# power_supply.net
KiCad netlist of a schematic drawn in Altium Designer
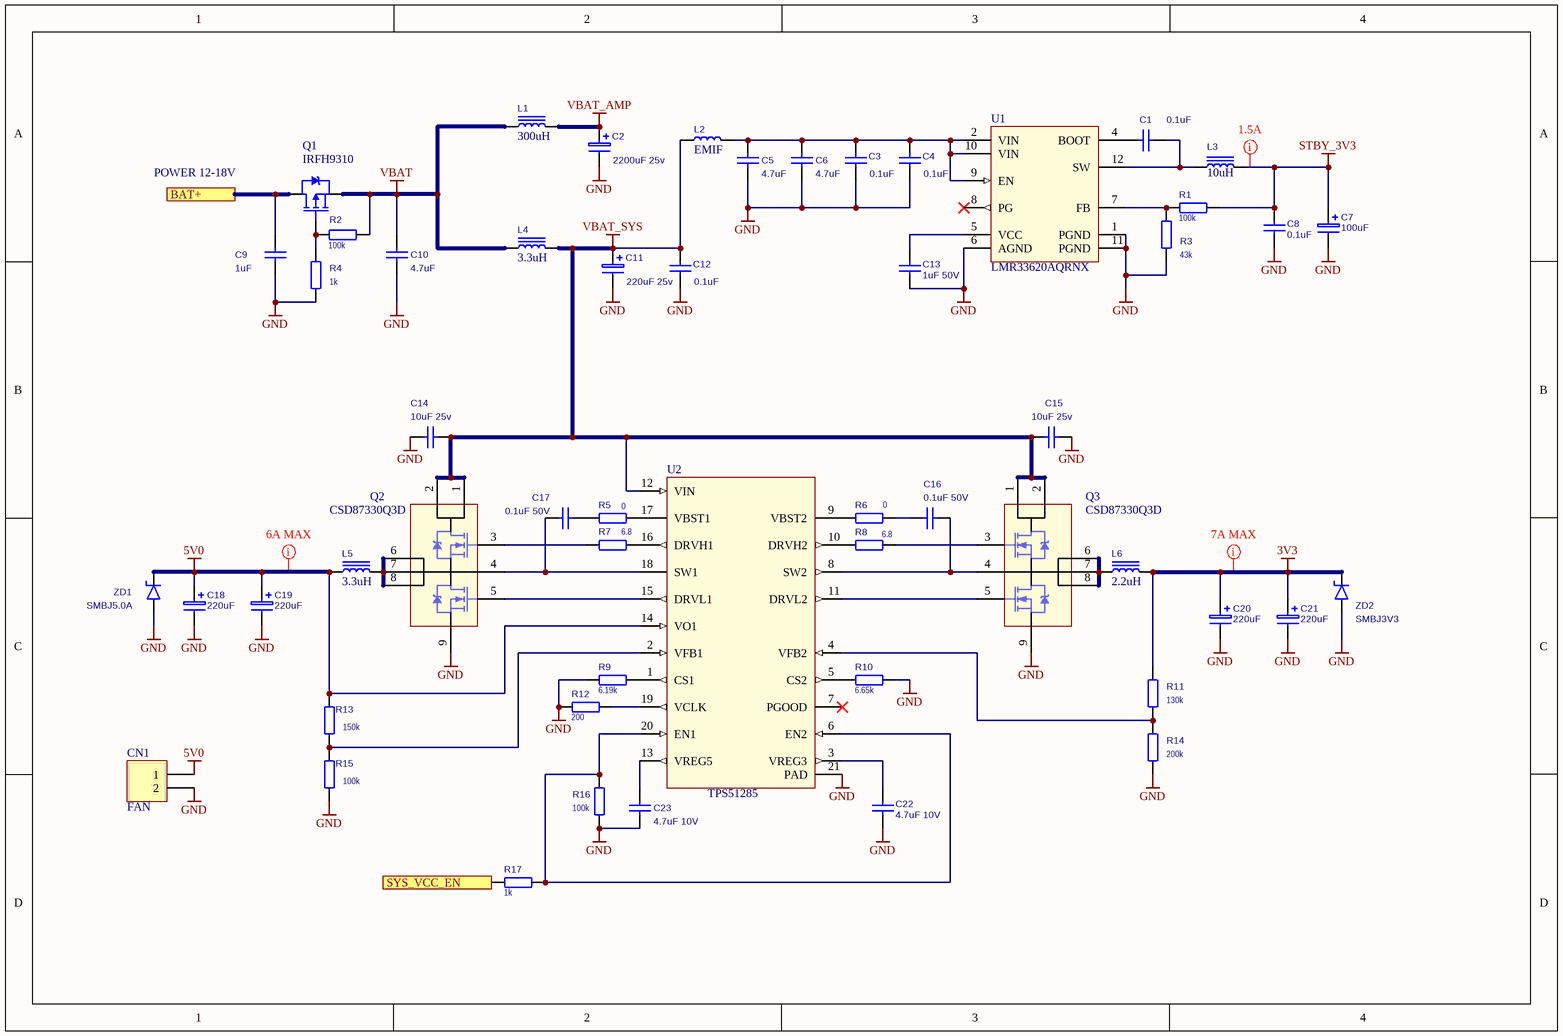
[diagram p0: power_supply.SchDoc]

(export (version "E")
  (design (tool "Eeschema 10.0.6"))
  (components
    (comp (ref "C1")
      (value "0.1uF")
      (footprint "Capacitors:C0603")
      (description "CAP_NPOL")
      (fields (field (name "Comment") "C1608X7R1H104K080AA"))
      (libsource (lib "capacitors") (part "CAP_NPOL"))
    )
    (comp (ref "C2")
      (value "2200uF 25v")
      (footprint "R12H05")
      (description "CAP_POL")
      (fields (field (name "Comment") "EEU-FC1V222"))
      (libsource (lib "capacitors") (part "CAP_POL"))
    )
    (comp (ref "C3")
      (value "0.1uF")
      (footprint "Capacitors:C0603")
      (description "CAP_NPOL")
      (fields (field (name "Comment") "C1608X7R1H104K080AA"))
      (libsource (lib "capacitors") (part "CAP_NPOL"))
    )
    (comp (ref "C4")
      (value "0.1uF")
      (footprint "Capacitors:C0603")
      (description "CAP_NPOL")
      (fields (field (name "Comment") "C1608X7R1H104K080AA"))
      (libsource (lib "capacitors") (part "CAP_NPOL"))
    )
    (comp (ref "C5")
      (value "4.7uF")
      (footprint "Capacitors:C0603")
      (description "CAP_NPOL")
      (fields (field (name "Comment") "GRM188R61E475KE11D"))
      (libsource (lib "capacitors") (part "CAP_NPOL"))
    )
    (comp (ref "C6")
      (value "4.7uF")
      (footprint "Capacitors:C0603")
      (description "CAP_NPOL")
      (fields (field (name "Comment") "GRM188R61E475KE11D"))
      (libsource (lib "capacitors") (part "CAP_NPOL"))
    )
    (comp (ref "C7")
      (value "100uF")
      (footprint "Capacitors:TANTAL-B-1411")
      (description "CAP_POL")
      (fields (field (name "Comment") "6TPE100MPB"))
      (libsource (lib "capacitors") (part "CAP_POL"))
    )
    (comp (ref "C8")
      (value "0.1uF")
      (footprint "Capacitors:C0603")
      (description "CAP_NPOL")
      (fields (field (name "Comment") "C1608X7R1H104K080AA"))
      (libsource (lib "capacitors") (part "CAP_NPOL"))
    )
    (comp (ref "C9")
      (value "1uF")
      (footprint "Capacitors:C0603")
      (description "CAP_NPOL")
      (fields (field (name "Comment") "CC0603KRX7R9BB105"))
      (libsource (lib "capacitors") (part "CAP_NPOL"))
    )
    (comp (ref "C10")
      (value "4.7uF")
      (footprint "Capacitors:C0603")
      (description "CAP_NPOL")
      (fields (field (name "Comment") "GRM188R61E475KE11D"))
      (libsource (lib "capacitors") (part "CAP_NPOL"))
    )
    (comp (ref "C11")
      (value "220uF 25v")
      (footprint "Capacitors:R08H04")
      (description "CAP_POL")
      (fields (field (name "Comment") "ECAP 220/25V 0812 105'C"))
      (libsource (lib "capacitors") (part "CAP_POL"))
    )
    (comp (ref "C12")
      (value "0.1uF")
      (footprint "Capacitors:C0603")
      (description "CAP_NPOL")
      (fields (field (name "Comment") "C1608X7R1H104K080AA"))
      (libsource (lib "capacitors") (part "CAP_NPOL"))
    )
    (comp (ref "C13")
      (value "1uF 50V")
      (footprint "Capacitors:C0603")
      (description "CAP_NPOL")
      (fields (field (name "Comment") "CC0603KRX7R9BB105"))
      (libsource (lib "capacitors") (part "CAP_NPOL"))
    )
    (comp (ref "C14")
      (value "10uF 25v")
      (footprint "Capacitors:C0805")
      (description "CAP_NPOL")
      (fields (field (name "Comment") "GRM21BR61E106KA73L"))
      (libsource (lib "capacitors") (part "CAP_NPOL"))
    )
    (comp (ref "C15")
      (value "10uF 25v")
      (footprint "Capacitors:C0805")
      (description "CAP_NPOL")
      (fields (field (name "Comment") "GRM21BR61E106KA73L"))
      (libsource (lib "capacitors") (part "CAP_NPOL"))
    )
    (comp (ref "C16")
      (value "0.1uF 50V")
      (footprint "Capacitors:C0603")
      (description "CAP_NPOL")
      (fields (field (name "Comment") "C1608X7R1H104K080AA"))
      (libsource (lib "capacitors") (part "CAP_NPOL"))
    )
    (comp (ref "C17")
      (value "0.1uF 50V")
      (footprint "Capacitors:C0603")
      (description "CAP_NPOL")
      (fields (field (name "Comment") "C1608X7R1H104K080AA"))
      (libsource (lib "capacitors") (part "CAP_NPOL"))
    )
    (comp (ref "C18")
      (value "220uF")
      (footprint "Capacitors:TANTAL-D-2916")
      (description "CAP_POL")
      (fields (field (name "Comment") "6TPE220MI"))
      (libsource (lib "capacitors") (part "CAP_POL"))
    )
    (comp (ref "C19")
      (value "220uF")
      (footprint "Capacitors:TANTAL-D-2916")
      (description "CAP_POL")
      (fields (field (name "Comment") "6TPE220MI"))
      (libsource (lib "capacitors") (part "CAP_POL"))
    )
    (comp (ref "C20")
      (value "220uF")
      (footprint "Capacitors:TANTAL-D-2916")
      (description "CAP_POL")
      (fields (field (name "Comment") "6TPE220MI"))
      (libsource (lib "capacitors") (part "CAP_POL"))
    )
    (comp (ref "C21")
      (value "220uF")
      (footprint "Capacitors:TANTAL-D-2916")
      (description "CAP_POL")
      (fields (field (name "Comment") "6TPE220MI"))
      (libsource (lib "capacitors") (part "CAP_POL"))
    )
    (comp (ref "C22")
      (value "4.7uF 10V")
      (footprint "Capacitors:C0603")
      (description "CAP_NPOL")
      (fields (field (name "Comment") "CL10A475KP8NNNC"))
      (libsource (lib "capacitors") (part "CAP_NPOL"))
    )
    (comp (ref "C23")
      (value "4.7uF 10V")
      (footprint "Capacitors:C0603")
      (description "CAP_NPOL")
      (fields (field (name "Comment") "CL10A475KP8NNNC"))
      (libsource (lib "capacitors") (part "CAP_NPOL"))
    )
    (comp (ref "CN1")
      (value "FAN")
      (footprint "HDR:MW-2M")
      (description "Header, 2-Pin")
      (fields (field (name "PUBLISHER") "Altium Limited"))
      (libsource (lib "HDR") (part "HDR 2"))
    )
    (comp (ref "L1")
      (value "300uH")
      (footprint "IND_COIL_TH_33x18")
      (description "IND_W_IRON")
      (fields (field (name "Comment") "ATCA-06-301M"))
      (libsource (lib "inductors") (part "IND_W_IRON"))
    )
    (comp (ref "L2")
      (value "EMIF")
      (footprint "IND0805")
      (description "IND_WO_IRON")
      (fields (field (name "Comment") "BLM21PG221SN1D"))
      (libsource (lib "inductors") (part "IND_WO_IRON"))
    )
    (comp (ref "L3")
      (value "10uH")
      (footprint "CDRH6D28")
      (fields (field (name "Comment") "CDRH6D38NP-100NC"))
      (libsource (lib "inductors") (part "IND_W_IRON"))
    )
    (comp (ref "L4")
      (value "3.3uH")
      (footprint "IHLP-2525CZ")
      (description "IND_W_IRON")
      (fields (field (name "Comment") "IHLP2525CZER3R3M01"))
      (libsource (lib "inductors") (part "IND_W_IRON"))
    )
    (comp (ref "L5")
      (value "3.3uH")
      (footprint "IHLP-2525CZ")
      (description "IND_W_IRON")
      (fields (field (name "Comment") "IHLP2525CZER3R3M01"))
      (libsource (lib "inductors") (part "IND_W_IRON"))
    )
    (comp (ref "L6")
      (value "2.2uH")
      (footprint "IHLP-2525CZ")
      (description "IND_W_IRON")
      (fields (field (name "Comment") "IHLP2525CZER2R2M01"))
      (libsource (lib "inductors") (part "IND_W_IRON"))
    )
    (comp (ref "Q1")
      (value "IRFH9310")
      (footprint "PQFN_5X6")
      (description "HEXFET Power MOSFET")
      (libsource (lib "MOSFET") (part "P-Channel"))
    )
    (comp (ref "Q2")
      (value "CSD87330Q3D")
      (footprint "SON:SON-8-3.3X3.3")
      (description "Synchronous Buck NexFET™ Power Block")
      (libsource (lib "CSD87330") (part "CSD87330Q3D"))
    )
    (comp (ref "Q3")
      (value "CSD87330Q3D")
      (footprint "SON:SON-8-3.3X3.3")
      (description "Synchronous Buck NexFET™ Power Block")
      (libsource (lib "CSD87330") (part "CSD87330Q3D"))
    )
    (comp (ref "R1")
      (value "100k")
      (footprint "R0603")
      (description "RES")
      (libsource (lib "resistors") (part "RESISTOR"))
    )
    (comp (ref "R2")
      (value "100k")
      (footprint "R0603")
      (description "RES")
      (libsource (lib "resistors") (part "RESISTOR"))
    )
    (comp (ref "R3")
      (value "43k")
      (footprint "R0603")
      (description "RES")
      (libsource (lib "resistors") (part "RESISTOR"))
    )
    (comp (ref "R4")
      (value "1k")
      (footprint "R0603")
      (description "RES")
      (libsource (lib "resistors") (part "RESISTOR"))
    )
    (comp (ref "R5")
      (value "0")
      (footprint "R0603")
      (description "RES")
      (libsource (lib "resistors") (part "RESISTOR"))
    )
    (comp (ref "R6")
      (value "0")
      (footprint "R0603")
      (description "RES")
      (libsource (lib "resistors") (part "RESISTOR"))
    )
    (comp (ref "R7")
      (value "6.8")
      (footprint "R0603")
      (description "RES")
      (fields (field (name "Comment") "RES 0603 6R8 5%"))
      (libsource (lib "resistors") (part "RESISTOR"))
    )
    (comp (ref "R8")
      (value "6.8")
      (footprint "R0603")
      (description "RES")
      (fields (field (name "Comment") "RES 0603 6R8 5%"))
      (libsource (lib "resistors") (part "RESISTOR"))
    )
    (comp (ref "R9")
      (value "6.19k")
      (footprint "R0603")
      (description "RES")
      (libsource (lib "resistors") (part "RESISTOR"))
    )
    (comp (ref "R10")
      (value "6.65k")
      (footprint "R0603")
      (description "RES")
      (libsource (lib "resistors") (part "RESISTOR"))
    )
    (comp (ref "R11")
      (value "130k")
      (footprint "R0603")
      (description "RES")
      (libsource (lib "resistors") (part "RESISTOR"))
    )
    (comp (ref "R12")
      (value "200")
      (footprint "R0603")
      (description "RES")
      (libsource (lib "resistors") (part "RESISTOR"))
    )
    (comp (ref "R13")
      (value "150k")
      (footprint "R0603")
      (description "RES")
      (libsource (lib "resistors") (part "RESISTOR"))
    )
    (comp (ref "R14")
      (value "200k")
      (footprint "R0603")
      (description "RES")
      (libsource (lib "resistors") (part "RESISTOR"))
    )
    (comp (ref "R15")
      (value "100k")
      (footprint "R0603")
      (description "RES")
      (libsource (lib "resistors") (part "RESISTOR"))
    )
    (comp (ref "R16")
      (value "100k")
      (footprint "R0603")
      (description "RES")
      (libsource (lib "resistors") (part "RESISTOR"))
    )
    (comp (ref "R17")
      (value "1k")
      (footprint "R0603")
      (description "RES")
      (libsource (lib "resistors") (part "RESISTOR"))
    )
    (comp (ref "U1")
      (value "LMR33620AQRNX")
      (footprint "QFN:VQFN-HR-12")
      (description "3.8-V to 36-V, 2-A Synchronous step-down voltage converter")
      (libsource (lib "LMR33620-Q1") (part "LMR33620-Q1"))
    )
    (comp (ref "U2")
      (value "TPS51285")
      (footprint "QFN:WQFN-20")
      (description "Ultra-Low Quiescent (ULQ™) Dual Synchronous Step-Down Controller with\r\n5V and 3.3V LDOs")
      (libsource (lib "TPS51285") (part "TPS51285"))
    )
    (comp (ref "ZD1")
      (value "SMBJ5.0A")
      (footprint "Diodes:SMB")
      (description "Zenner diode")
      (fields (field (name "Comment") "SMBJ5.0A-TR"))
      (libsource (lib "diodes") (part "ZENNER"))
    )
    (comp (ref "ZD2")
      (value "SMBJ3V3")
      (footprint "Diodes:SMB")
      (description "Zenner diode")
      (libsource (lib "diodes") (part "ZENNER"))
    )
  )
  (nets
    (net (code "1") (name "/BAT+") (class "Default")
      (node (ref "C9") (pin "2") (pinfunction "2_2") (pintype "passive"))
      (node (ref "Q1") (pin "3") (pinfunction "D_3") (pintype "passive"))
    )
    (net (code "2") (name "/SYS_VCC_EN") (class "Default")
      (node (ref "R17") (pin "1") (pinfunction "1_1") (pintype "passive"))
    )
    (net (code "3") (name "3V3") (class "Default")
      (node (ref "C20") (pin "1") (pinfunction "+_1") (pintype "passive"))
      (node (ref "C21") (pin "1") (pinfunction "+_1") (pintype "passive"))
      (node (ref "L6") (pin "2") (pintype "passive"))
      (node (ref "R11") (pin "1") (pinfunction "1_1") (pintype "passive"))
      (node (ref "ZD2") (pin "2") (pinfunction "K_2") (pintype "passive"))
    )
    (net (code "4") (name "5V0") (class "Default")
      (node (ref "C18") (pin "1") (pinfunction "+_1") (pintype "passive"))
      (node (ref "C19") (pin "1") (pinfunction "+_1") (pintype "passive"))
      (node (ref "CN1") (pin "1") (pinfunction "1_1") (pintype "passive"))
      (node (ref "L5") (pin "1") (pintype "passive"))
      (node (ref "R13") (pin "1") (pinfunction "1_1") (pintype "passive"))
      (node (ref "U2") (pin "14") (pinfunction "VO1_14") (pintype "input"))
      (node (ref "ZD1") (pin "2") (pinfunction "K_2") (pintype "passive"))
    )
    (net (code "5") (name "GND") (class "Default")
      (node (ref "C10") (pin "1") (pinfunction "1_1") (pintype "passive"))
      (node (ref "C11") (pin "2") (pinfunction "-_2") (pintype "passive"))
      (node (ref "C12") (pin "2") (pinfunction "2_2") (pintype "passive"))
      (node (ref "C13") (pin "1") (pinfunction "1_1") (pintype "passive"))
      (node (ref "C14") (pin "1") (pinfunction "1_1") (pintype "passive"))
      (node (ref "C15") (pin "2") (pinfunction "2_2") (pintype "passive"))
      (node (ref "C18") (pin "2") (pinfunction "-_2") (pintype "passive"))
      (node (ref "C19") (pin "2") (pinfunction "-_2") (pintype "passive"))
      (node (ref "C2") (pin "2") (pinfunction "-_2") (pintype "passive"))
      (node (ref "C20") (pin "2") (pinfunction "-_2") (pintype "passive"))
      (node (ref "C21") (pin "2") (pinfunction "-_2") (pintype "passive"))
      (node (ref "C22") (pin "2") (pinfunction "2_2") (pintype "passive"))
      (node (ref "C23") (pin "2") (pinfunction "2_2") (pintype "passive"))
      (node (ref "C3") (pin "2") (pinfunction "2_2") (pintype "passive"))
      (node (ref "C4") (pin "2") (pinfunction "2_2") (pintype "passive"))
      (node (ref "C5") (pin "1") (pinfunction "1_1") (pintype "passive"))
      (node (ref "C6") (pin "1") (pinfunction "1_1") (pintype "passive"))
      (node (ref "C7") (pin "2") (pinfunction "-_2") (pintype "passive"))
      (node (ref "C8") (pin "2") (pinfunction "2_2") (pintype "passive"))
      (node (ref "C9") (pin "1") (pinfunction "1_1") (pintype "passive"))
      (node (ref "CN1") (pin "2") (pinfunction "2_2") (pintype "passive"))
      (node (ref "Q2") (pin "9") (pinfunction "GND_9") (pintype "passive"))
      (node (ref "Q3") (pin "9") (pinfunction "GND_9") (pintype "passive"))
      (node (ref "R10") (pin "2") (pinfunction "2_2") (pintype "passive"))
      (node (ref "R12") (pin "1") (pinfunction "1_1") (pintype "passive"))
      (node (ref "R14") (pin "2") (pinfunction "2_2") (pintype "passive"))
      (node (ref "R15") (pin "2") (pinfunction "2_2") (pintype "passive"))
      (node (ref "R16") (pin "1") (pinfunction "1_1") (pintype "passive"))
      (node (ref "R3") (pin "2") (pinfunction "2_2") (pintype "passive"))
      (node (ref "R4") (pin "2") (pinfunction "2_2") (pintype "passive"))
      (node (ref "R9") (pin "1") (pinfunction "1_1") (pintype "passive"))
      (node (ref "U1") (pin "1") (pinfunction "PGND_1") (pintype "power_in"))
      (node (ref "U1") (pin "11") (pinfunction "PGND_11") (pintype "power_in"))
      (node (ref "U1") (pin "6") (pinfunction "AGND_6") (pintype "power_in"))
      (node (ref "U2") (pin "21") (pinfunction "PAD_21") (pintype "power_in"))
      (node (ref "ZD1") (pin "1") (pinfunction "A_1") (pintype "passive"))
      (node (ref "ZD2") (pin "1") (pinfunction "A_1") (pintype "passive"))
    )
    (net (code "6") (name "Net-(C16-Pad1)") (class "Default")
      (node (ref "C16") (pin "1") (pinfunction "1_1") (pintype "passive"))
      (node (ref "R6") (pin "1") (pinfunction "1_1") (pintype "passive"))
    )
    (net (code "7") (name "Net-(C17-Pad1)") (class "Default")
      (node (ref "C17") (pin "1") (pinfunction "1_1") (pintype "passive"))
      (node (ref "R5") (pin "1") (pinfunction "1_1") (pintype "passive"))
    )
    (net (code "8") (name "Net-(L5-Pad2)") (class "Default")
      (node (ref "L5") (pin "2") (pintype "passive"))
      (node (ref "Q2") (pin "6") (pinfunction "VSW_6") (pintype "passive"))
      (node (ref "Q2") (pin "7") (pinfunction "VSW_7") (pintype "passive"))
      (node (ref "Q2") (pin "8") (pinfunction "VSW_8") (pintype "passive"))
    )
    (net (code "9") (name "Net-(L6-Pad1)") (class "Default")
      (node (ref "L6") (pin "1") (pintype "passive"))
      (node (ref "Q3") (pin "6") (pinfunction "VSW_6") (pintype "passive"))
      (node (ref "Q3") (pin "7") (pinfunction "VSW_7") (pintype "passive"))
      (node (ref "Q3") (pin "8") (pinfunction "VSW_8") (pintype "passive"))
    )
    (net (code "10") (name "Net-(Q1-G)") (class "Default")
      (node (ref "Q1") (pin "1") (pinfunction "G_1") (pintype "passive"))
      (node (ref "R2") (pin "1") (pinfunction "1_1") (pintype "passive"))
      (node (ref "R4") (pin "1") (pinfunction "1_1") (pintype "passive"))
    )
    (net (code "11") (name "Net-(Q2-BG)") (class "Default")
      (node (ref "Q2") (pin "5") (pinfunction "BG_5") (pintype "passive"))
      (node (ref "U2") (pin "15") (pinfunction "DRVL1_15") (pintype "output"))
    )
    (net (code "12") (name "Net-(Q2-TG)") (class "Default")
      (node (ref "Q2") (pin "3") (pinfunction "TG_3") (pintype "passive"))
      (node (ref "R7") (pin "1") (pinfunction "1_1") (pintype "passive"))
    )
    (net (code "13") (name "Net-(Q2-TGR)") (class "Default")
      (node (ref "C17") (pin "2") (pinfunction "2_2") (pintype "passive"))
      (node (ref "Q2") (pin "4") (pinfunction "TGR_4") (pintype "passive"))
      (node (ref "U2") (pin "18") (pinfunction "SW1_18") (pintype "passive"))
    )
    (net (code "14") (name "Net-(Q3-BG)") (class "Default")
      (node (ref "Q3") (pin "5") (pinfunction "BG_5") (pintype "passive"))
      (node (ref "U2") (pin "11") (pinfunction "DRVL2_11") (pintype "output"))
    )
    (net (code "15") (name "Net-(Q3-TG)") (class "Default")
      (node (ref "Q3") (pin "3") (pinfunction "TG_3") (pintype "passive"))
      (node (ref "R8") (pin "1") (pinfunction "1_1") (pintype "passive"))
    )
    (net (code "16") (name "Net-(Q3-TGR)") (class "Default")
      (node (ref "C16") (pin "2") (pinfunction "2_2") (pintype "passive"))
      (node (ref "Q3") (pin "4") (pinfunction "TGR_4") (pintype "passive"))
      (node (ref "U2") (pin "8") (pinfunction "SW2_8") (pintype "output"))
    )
    (net (code "17") (name "Net-(U1-BOOT)") (class "Default")
      (node (ref "C1") (pin "2") (pinfunction "2_2") (pintype "passive"))
      (node (ref "U1") (pin "4") (pinfunction "BOOT_4") (pintype "passive"))
    )
    (net (code "18") (name "Net-(U1-EN)") (class "Default")
      (node (ref "C3") (pin "1") (pinfunction "1_1") (pintype "passive"))
      (node (ref "C4") (pin "1") (pinfunction "1_1") (pintype "passive"))
      (node (ref "C5") (pin "2") (pinfunction "2_2") (pintype "passive"))
      (node (ref "C6") (pin "2") (pinfunction "2_2") (pintype "passive"))
      (node (ref "L2") (pin "1") (pintype "passive"))
      (node (ref "U1") (pin "10") (pinfunction "VIN_10") (pintype "power_in"))
      (node (ref "U1") (pin "2") (pinfunction "VIN_2") (pintype "power_in"))
      (node (ref "U1") (pin "9") (pinfunction "EN_9") (pintype "input"))
    )
    (net (code "19") (name "Net-(U1-FB)") (class "Default")
      (node (ref "R1") (pin "1") (pinfunction "1_1") (pintype "passive"))
      (node (ref "R3") (pin "1") (pinfunction "1_1") (pintype "passive"))
      (node (ref "U1") (pin "7") (pinfunction "FB_7") (pintype "passive"))
    )
    (net (code "20") (name "Net-(U1-SW)") (class "Default")
      (node (ref "C1") (pin "1") (pinfunction "1_1") (pintype "passive"))
      (node (ref "L3") (pin "1") (pintype "passive"))
      (node (ref "U1") (pin "12") (pinfunction "SW_12") (pintype "power_in"))
    )
    (net (code "21") (name "Net-(U1-VCC)") (class "Default")
      (node (ref "C13") (pin "2") (pinfunction "2_2") (pintype "passive"))
      (node (ref "U1") (pin "5") (pinfunction "VCC_5") (pintype "power_in"))
    )
    (net (code "22") (name "Net-(U2-CS1)") (class "Default")
      (node (ref "R9") (pin "2") (pinfunction "2_2") (pintype "passive"))
      (node (ref "U2") (pin "1") (pinfunction "CS1_1") (pintype "output"))
    )
    (net (code "23") (name "Net-(U2-CS2)") (class "Default")
      (node (ref "R10") (pin "1") (pinfunction "1_1") (pintype "passive"))
      (node (ref "U2") (pin "5") (pinfunction "CS2_5") (pintype "output"))
    )
    (net (code "24") (name "Net-(U2-DRVH1)") (class "Default")
      (node (ref "R7") (pin "2") (pinfunction "2_2") (pintype "passive"))
      (node (ref "U2") (pin "16") (pinfunction "DRVH1_16") (pintype "output"))
    )
    (net (code "25") (name "Net-(U2-DRVH2)") (class "Default")
      (node (ref "R8") (pin "2") (pinfunction "2_2") (pintype "passive"))
      (node (ref "U2") (pin "10") (pinfunction "DRVH2_10") (pintype "output"))
    )
    (net (code "26") (name "Net-(U2-EN1)") (class "Default")
      (node (ref "R16") (pin "2") (pinfunction "2_2") (pintype "passive"))
      (node (ref "R17") (pin "2") (pinfunction "2_2") (pintype "passive"))
      (node (ref "U2") (pin "20") (pinfunction "EN1_20") (pintype "input"))
      (node (ref "U2") (pin "6") (pinfunction "EN2_6") (pintype "input"))
    )
    (net (code "27") (name "Net-(U2-VBST1)") (class "Default")
      (node (ref "R5") (pin "2") (pinfunction "2_2") (pintype "passive"))
      (node (ref "U2") (pin "17") (pinfunction "VBST1_17") (pintype "passive"))
    )
    (net (code "28") (name "Net-(U2-VBST2)") (class "Default")
      (node (ref "R6") (pin "2") (pinfunction "2_2") (pintype "passive"))
      (node (ref "U2") (pin "9") (pinfunction "VBST2_9") (pintype "passive"))
    )
    (net (code "29") (name "Net-(U2-VCLK)") (class "Default")
      (node (ref "R12") (pin "2") (pinfunction "2_2") (pintype "passive"))
      (node (ref "U2") (pin "19") (pinfunction "VCLK_19") (pintype "output"))
    )
    (net (code "30") (name "Net-(U2-VFB1)") (class "Default")
      (node (ref "R13") (pin "2") (pinfunction "2_2") (pintype "passive"))
      (node (ref "R15") (pin "1") (pinfunction "1_1") (pintype "passive"))
      (node (ref "U2") (pin "2") (pinfunction "VFB1_2") (pintype "input"))
    )
    (net (code "31") (name "Net-(U2-VFB2)") (class "Default")
      (node (ref "R11") (pin "2") (pinfunction "2_2") (pintype "passive"))
      (node (ref "R14") (pin "1") (pinfunction "1_1") (pintype "passive"))
      (node (ref "U2") (pin "4") (pinfunction "VFB2_4") (pintype "input"))
    )
    (net (code "32") (name "Net-(U2-VREG3)") (class "Default")
      (node (ref "C22") (pin "1") (pinfunction "1_1") (pintype "passive"))
      (node (ref "U2") (pin "3") (pinfunction "VREG3_3") (pintype "output"))
    )
    (net (code "33") (name "Net-(U2-VREG5)") (class "Default")
      (node (ref "C23") (pin "1") (pinfunction "1_1") (pintype "passive"))
      (node (ref "U2") (pin "13") (pinfunction "VREG5_13") (pintype "output"))
    )
    (net (code "34") (name "STBY_3V3") (class "Default")
      (node (ref "C7") (pin "1") (pinfunction "+_1") (pintype "passive"))
      (node (ref "C8") (pin "1") (pinfunction "1_1") (pintype "passive"))
      (node (ref "L3") (pin "2") (pintype "passive"))
      (node (ref "R1") (pin "2") (pinfunction "2_2") (pintype "passive"))
    )
    (net (code "35") (name "VBAT") (class "Default")
      (node (ref "C10") (pin "2") (pinfunction "2_2") (pintype "passive"))
      (node (ref "L1") (pin "1") (pintype "passive"))
      (node (ref "L4") (pin "1") (pintype "passive"))
      (node (ref "Q1") (pin "2") (pinfunction "S_2") (pintype "passive"))
      (node (ref "R2") (pin "2") (pinfunction "2_2") (pintype "passive"))
    )
    (net (code "36") (name "VBAT_AMP") (class "Default")
      (node (ref "C2") (pin "1") (pinfunction "+_1") (pintype "passive"))
      (node (ref "L1") (pin "2") (pintype "passive"))
    )
    (net (code "37") (name "VBAT_SYS") (class "Default")
      (node (ref "C11") (pin "1") (pinfunction "+_1") (pintype "passive"))
      (node (ref "C12") (pin "1") (pinfunction "1_1") (pintype "passive"))
      (node (ref "C14") (pin "2") (pinfunction "2_2") (pintype "passive"))
      (node (ref "C15") (pin "1") (pinfunction "1_1") (pintype "passive"))
      (node (ref "L2") (pin "2") (pintype "passive"))
      (node (ref "L4") (pin "2") (pintype "passive"))
      (node (ref "Q2") (pin "1") (pinfunction "VIN_1") (pintype "passive"))
      (node (ref "Q2") (pin "2") (pinfunction "2_2") (pintype "passive"))
      (node (ref "Q3") (pin "1") (pinfunction "VIN_1") (pintype "passive"))
      (node (ref "Q3") (pin "2") (pinfunction "2_2") (pintype "passive"))
      (node (ref "U2") (pin "12") (pinfunction "VIN_12") (pintype "input"))
    )
    (net (code "38") (name "unconnected-(U1-PG-Pad8)") (class "Default")
      (node (ref "U1") (pin "8") (pinfunction "PG_8") (pintype "output+no_connect"))
    )
    (net (code "39") (name "unconnected-(U2-PGOOD-Pad7)") (class "Default")
      (node (ref "U2") (pin "7") (pinfunction "PGOOD_7") (pintype "open_collector+no_connect"))
    )
  )
)
